# MINIRACER-IMU.net
KiCad netlist of a schematic drawn in Altium Designer
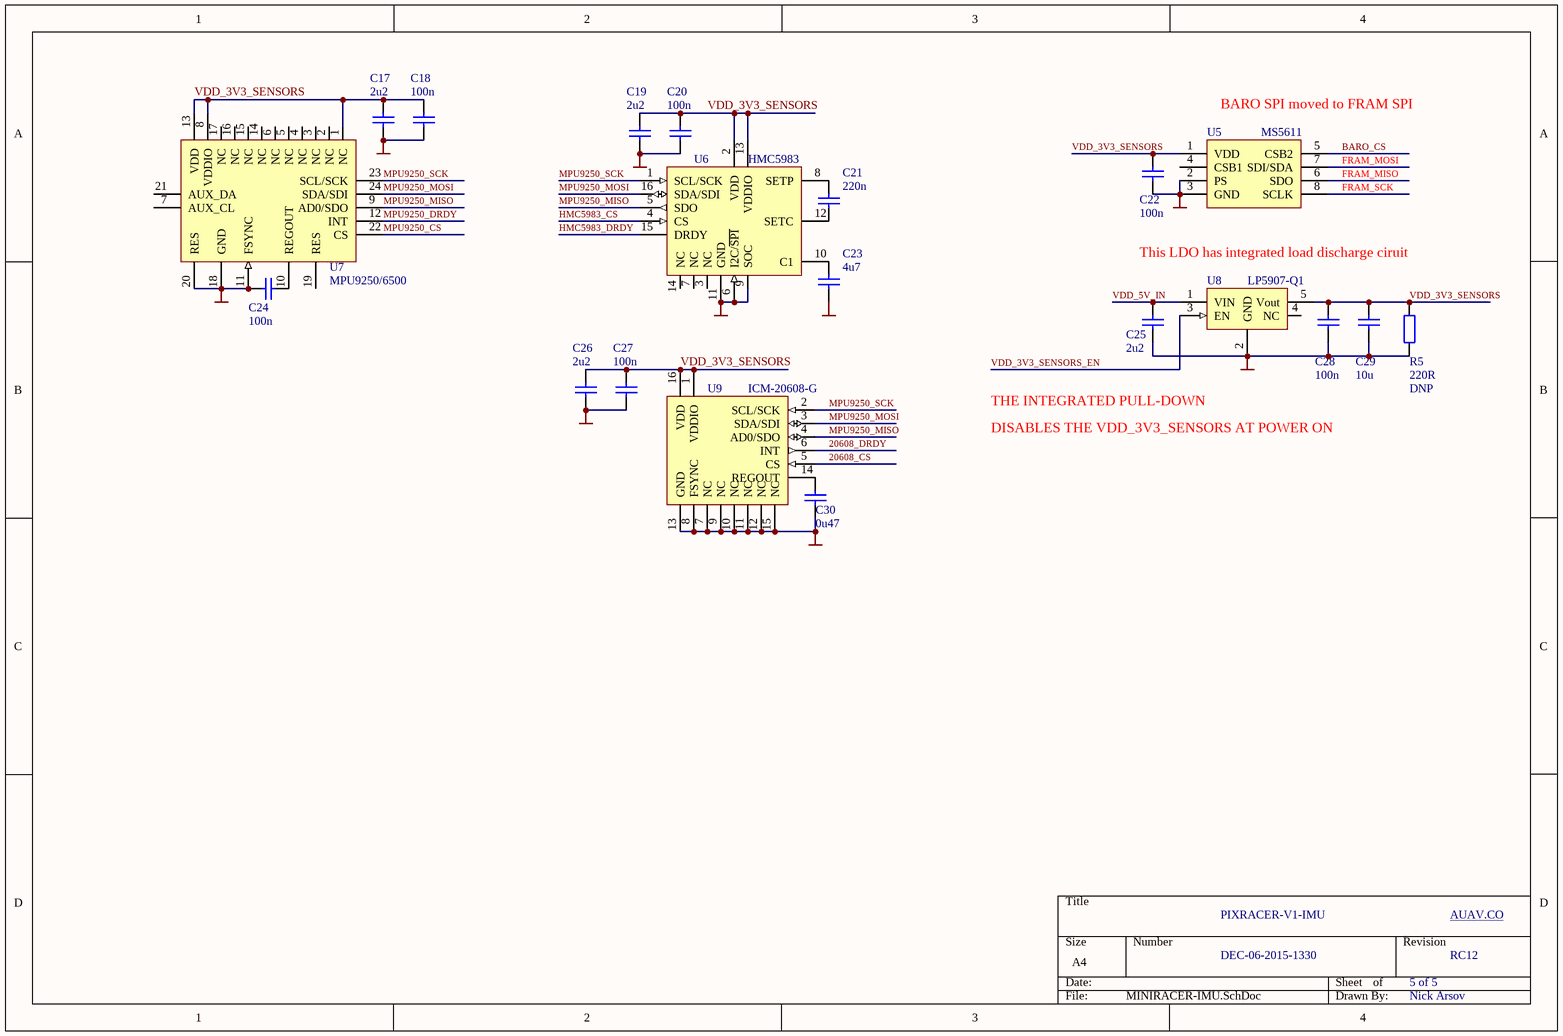
[diagram p0: MINIRACER-IMU.SchDoc]

(export (version "E")
  (design (tool "Eeschema 10.0.6"))
  (components
    (comp (ref "C17")
      (value "2u2")
      (footprint "0402A")
      (description "Capacitor")
      (fields (field (name "PUBLISHER") "Altium Limited"))
      (libsource (lib "Miscellaneous Devices") (part "Cap"))
    )
    (comp (ref "C18")
      (value "100n")
      (footprint "0402A")
      (description "Capacitor")
      (fields (field (name "PUBLISHER") "Altium Limited"))
      (libsource (lib "Miscellaneous Devices") (part "Cap"))
    )
    (comp (ref "C19")
      (value "2u2")
      (footprint "0402A")
      (description "Capacitor")
      (fields (field (name "PUBLISHER") "Altium Limited"))
      (libsource (lib "Miscellaneous Devices") (part "Cap"))
    )
    (comp (ref "C20")
      (value "100n")
      (footprint "0402A")
      (description "Capacitor")
      (fields (field (name "PUBLISHER") "Altium Limited"))
      (libsource (lib "Miscellaneous Devices") (part "Cap"))
    )
    (comp (ref "C21")
      (value "220n")
      (footprint "0402A")
      (description "Capacitor")
      (fields (field (name "PUBLISHER") "Altium Limited"))
      (libsource (lib "Miscellaneous Devices") (part "Cap"))
    )
    (comp (ref "C22")
      (value "100n")
      (footprint "0402A")
      (description "Capacitor")
      (fields (field (name "PUBLISHER") "Altium Limited"))
      (libsource (lib "Miscellaneous Devices") (part "Cap"))
    )
    (comp (ref "C23")
      (value "4u7")
      (footprint "0603A")
      (description "Capacitor")
      (fields (field (name "PUBLISHER") "Altium Limited"))
      (libsource (lib "Miscellaneous Devices") (part "Cap"))
    )
    (comp (ref "C24")
      (value "100n")
      (footprint "0402A")
      (description "Capacitor")
      (fields (field (name "PUBLISHER") "Altium Limited"))
      (libsource (lib "Miscellaneous Devices") (part "Cap"))
    )
    (comp (ref "C25")
      (value "2u2")
      (footprint "0603A")
      (description "Capacitor")
      (fields (field (name "PUBLISHER") "Altium Limited"))
      (libsource (lib "Miscellaneous Devices") (part "Cap"))
    )
    (comp (ref "C26")
      (value "2u2")
      (footprint "0402A")
      (description "Capacitor")
      (fields (field (name "PUBLISHER") "Altium Limited"))
      (libsource (lib "Miscellaneous Devices") (part "Cap"))
    )
    (comp (ref "C27")
      (value "100n")
      (footprint "0402A")
      (description "Capacitor")
      (fields (field (name "PUBLISHER") "Altium Limited"))
      (libsource (lib "Miscellaneous Devices") (part "Cap"))
    )
    (comp (ref "C28")
      (value "100n")
      (footprint "0603A")
      (description "Capacitor")
      (fields (field (name "PUBLISHER") "Altium Limited"))
      (libsource (lib "Miscellaneous Devices") (part "Cap"))
    )
    (comp (ref "C29")
      (value "10u")
      (footprint "0603A")
      (description "Capacitor")
      (fields (field (name "PUBLISHER") "Altium Limited"))
      (libsource (lib "Miscellaneous Devices") (part "Cap"))
    )
    (comp (ref "C30")
      (value "0u47")
      (footprint "0402A")
      (description "Capacitor")
      (fields (field (name "PUBLISHER") "Altium Limited"))
      (libsource (lib "Miscellaneous Devices") (part "Cap"))
    )
    (comp (ref "R5")
      (value "220R")
      (footprint "0402A")
      (description "Resistor")
      (fields (field (name "REM") "DNP") (field (name "PUBLISHER") "Altium Limited"))
      (libsource (lib "Miscellaneous Devices") (part "Res2"))
    )
    (comp (ref "U5")
      (value "MS5611")
      (footprint "MS5611")
      (libsource (lib "My_Altium") (part "MS5611-01BA03"))
    )
    (comp (ref "U6") (value "HMC5983") (footprint "HMC5883L") (libsource (lib "My_Altium") (part "HMC5983")))
    (comp (ref "U7")
      (value "MPU9250/6500")
      (footprint "MPU6500-9250")
      (libsource (lib "My_Altium") (part "MPU6500"))
    )
    (comp (ref "U8")
      (value "LP5907-Q1")
      (footprint "SOT23-5")
      (libsource (lib "My_Altium") (part "LP5907-Q1"))
    )
    (comp (ref "U9")
      (value "ICM-20608-G")
      (footprint "HCLGA-16L")
      (libsource (lib "My_Altium") (part "ICM-20608-G"))
    )
  )
  (nets
    (net (code "1") (name "/20608_CS") (class "Default")
      (node (ref "U9") (pin "5") (pinfunction "CS_5") (pintype "input"))
    )
    (net (code "2") (name "/20608_DRDY") (class "Default")
      (node (ref "U9") (pin "6") (pinfunction "INT_6") (pintype "output"))
    )
    (net (code "3") (name "/BARO_CS") (class "Default")
      (node (ref "U5") (pin "5") (pinfunction "CSB2_5") (pintype "passive"))
    )
    (net (code "4") (name "/FRAM_MISO") (class "Default")
      (node (ref "U5") (pin "6") (pinfunction "SDO_6") (pintype "passive"))
    )
    (net (code "5") (name "/FRAM_MOSI") (class "Default")
      (node (ref "U5") (pin "7") (pinfunction "SDI/SDA_7") (pintype "passive"))
    )
    (net (code "6") (name "/FRAM_SCK") (class "Default")
      (node (ref "U5") (pin "8") (pinfunction "SCLK_8") (pintype "passive"))
    )
    (net (code "7") (name "/HMC5983_CS") (class "Default")
      (node (ref "U6") (pin "4") (pinfunction "CS_4") (pintype "input"))
    )
    (net (code "8") (name "/HMC5983_DRDY") (class "Default")
      (node (ref "U6") (pin "15") (pinfunction "DRDY_15") (pintype "passive"))
    )
    (net (code "9") (name "/MPU9250_CS") (class "Default")
      (node (ref "U7") (pin "22") (pinfunction "CS_22") (pintype "passive"))
    )
    (net (code "10") (name "/MPU9250_DRDY") (class "Default")
      (node (ref "U7") (pin "12") (pinfunction "INT_12") (pintype "passive"))
    )
    (net (code "11") (name "/MPU9250_MISO") (class "Default")
      (node (ref "U6") (pin "5") (pinfunction "SDO_5") (pintype "output"))
      (node (ref "U7") (pin "9") (pinfunction "AD0/SDO_9") (pintype "passive"))
      (node (ref "U9") (pin "4") (pinfunction "AD0/SDO_4") (pintype "bidirectional"))
    )
    (net (code "12") (name "/MPU9250_MOSI") (class "Default")
      (node (ref "U6") (pin "16") (pinfunction "SDA/SDI_16") (pintype "bidirectional"))
      (node (ref "U7") (pin "24") (pinfunction "SDA/SDI_24") (pintype "passive"))
      (node (ref "U9") (pin "3") (pinfunction "SDA/SDI_3") (pintype "bidirectional"))
    )
    (net (code "13") (name "/MPU9250_SCK") (class "Default")
      (node (ref "U6") (pin "1") (pinfunction "SCL/SCK_1") (pintype "input"))
      (node (ref "U7") (pin "23") (pinfunction "SCL/SCK_23") (pintype "passive"))
      (node (ref "U9") (pin "2") (pinfunction "SCL/SCK_2") (pintype "input"))
    )
    (net (code "14") (name "/VDD_3V3_SENSORS") (class "Default")
      (node (ref "C17") (pin "2") (pinfunction "2_2") (pintype "passive"))
      (node (ref "C18") (pin "2") (pinfunction "2_2") (pintype "passive"))
      (node (ref "C19") (pin "2") (pinfunction "2_2") (pintype "passive"))
      (node (ref "C20") (pin "2") (pinfunction "2_2") (pintype "passive"))
      (node (ref "C22") (pin "2") (pinfunction "2_2") (pintype "passive"))
      (node (ref "C26") (pin "2") (pinfunction "2_2") (pintype "passive"))
      (node (ref "C27") (pin "2") (pinfunction "2_2") (pintype "passive"))
      (node (ref "C28") (pin "2") (pinfunction "2_2") (pintype "passive"))
      (node (ref "C29") (pin "2") (pinfunction "2_2") (pintype "passive"))
      (node (ref "R5") (pin "2") (pinfunction "2_2") (pintype "passive"))
      (node (ref "U5") (pin "1") (pinfunction "VDD_1") (pintype "power_in"))
      (node (ref "U6") (pin "13") (pinfunction "VDDIO_13") (pintype "power_in"))
      (node (ref "U6") (pin "2") (pinfunction "VDD_2") (pintype "power_in"))
      (node (ref "U7") (pin "1") (pinfunction "NC_1") (pintype "passive"))
      (node (ref "U7") (pin "13") (pinfunction "VDD_13") (pintype "power_in"))
      (node (ref "U7") (pin "8") (pinfunction "VDDIO_8") (pintype "power_in"))
      (node (ref "U8") (pin "5") (pinfunction "Vout_5") (pintype "power_in"))
      (node (ref "U9") (pin "1") (pinfunction "VDDIO_1") (pintype "power_in"))
      (node (ref "U9") (pin "16") (pinfunction "VDD_16") (pintype "power_in"))
    )
    (net (code "15") (name "/VDD_3V3_SENSORS_EN") (class "Default")
      (node (ref "U8") (pin "3") (pinfunction "EN_3") (pintype "input"))
    )
    (net (code "16") (name "/VDD_5V_IN") (class "Default")
      (node (ref "C25") (pin "2") (pinfunction "2_2") (pintype "passive"))
      (node (ref "U8") (pin "1") (pinfunction "VIN_1") (pintype "power_in"))
    )
    (net (code "17") (name "GND") (class "Default")
      (node (ref "C17") (pin "1") (pinfunction "1_1") (pintype "passive"))
      (node (ref "C18") (pin "1") (pinfunction "1_1") (pintype "passive"))
      (node (ref "C19") (pin "1") (pinfunction "1_1") (pintype "passive"))
      (node (ref "C20") (pin "1") (pinfunction "1_1") (pintype "passive"))
      (node (ref "C22") (pin "1") (pinfunction "1_1") (pintype "passive"))
      (node (ref "C23") (pin "1") (pinfunction "1_1") (pintype "passive"))
      (node (ref "C24") (pin "1") (pinfunction "1_1") (pintype "passive"))
      (node (ref "C25") (pin "1") (pinfunction "1_1") (pintype "passive"))
      (node (ref "C26") (pin "1") (pinfunction "1_1") (pintype "passive"))
      (node (ref "C27") (pin "1") (pinfunction "1_1") (pintype "passive"))
      (node (ref "C28") (pin "1") (pinfunction "1_1") (pintype "passive"))
      (node (ref "C29") (pin "1") (pinfunction "1_1") (pintype "passive"))
      (node (ref "C30") (pin "1") (pinfunction "1_1") (pintype "passive"))
      (node (ref "R5") (pin "1") (pinfunction "1_1") (pintype "passive"))
      (node (ref "U5") (pin "2") (pinfunction "PS_2") (pintype "passive"))
      (node (ref "U5") (pin "3") (pinfunction "GND_3") (pintype "power_in"))
      (node (ref "U6") (pin "11") (pinfunction "GND_11") (pintype "power_in"))
      (node (ref "U6") (pin "6") (pinfunction "I2C/~{SPI}_6") (pintype "input"))
      (node (ref "U6") (pin "9") (pinfunction "SOC_9") (pintype "power_in"))
      (node (ref "U7") (pin "11") (pinfunction "FSYNC_11") (pintype "input"))
      (node (ref "U7") (pin "18") (pinfunction "GND_18") (pintype "power_in"))
      (node (ref "U7") (pin "20") (pinfunction "RES_20") (pintype "passive"))
      (node (ref "U8") (pin "2") (pinfunction "GND_2") (pintype "power_in"))
      (node (ref "U9") (pin "10") (pinfunction "NC_10") (pintype "passive"))
      (node (ref "U9") (pin "11") (pinfunction "NC_11") (pintype "passive"))
      (node (ref "U9") (pin "12") (pinfunction "NC_12") (pintype "passive"))
      (node (ref "U9") (pin "13") (pinfunction "GND_13") (pintype "power_in"))
      (node (ref "U9") (pin "15") (pinfunction "NC_15") (pintype "passive"))
      (node (ref "U9") (pin "7") (pinfunction "NC_7") (pintype "passive"))
      (node (ref "U9") (pin "8") (pinfunction "FSYNC_8") (pintype "passive"))
      (node (ref "U9") (pin "9") (pinfunction "NC_9") (pintype "passive"))
    )
    (net (code "18") (name "Net-(U6-C1)") (class "Default")
      (node (ref "C23") (pin "2") (pinfunction "2_2") (pintype "passive"))
      (node (ref "U6") (pin "10") (pinfunction "C1_10") (pintype "passive"))
    )
    (net (code "19") (name "Net-(U6-SETC)") (class "Default")
      (node (ref "C21") (pin "1") (pinfunction "1_1") (pintype "passive"))
      (node (ref "U6") (pin "12") (pinfunction "SETC_12") (pintype "passive"))
    )
    (net (code "20") (name "Net-(U6-SETP)") (class "Default")
      (node (ref "C21") (pin "2") (pinfunction "2_2") (pintype "passive"))
      (node (ref "U6") (pin "8") (pinfunction "SETP_8") (pintype "passive"))
    )
    (net (code "21") (name "Net-(U7-REGOUT)") (class "Default")
      (node (ref "C24") (pin "2") (pinfunction "2_2") (pintype "passive"))
      (node (ref "U7") (pin "10") (pinfunction "REGOUT_10") (pintype "passive"))
    )
    (net (code "22") (name "Net-(U9-REGOUT)") (class "Default")
      (node (ref "C30") (pin "2") (pinfunction "2_2") (pintype "passive"))
      (node (ref "U9") (pin "14") (pinfunction "REGOUT_14") (pintype "passive"))
    )
    (net (code "23") (name "unconnected-(U5-CSB1-Pad4)") (class "Default")
      (node (ref "U5") (pin "4") (pinfunction "CSB1_4") (pintype "passive"))
    )
    (net (code "24") (name "unconnected-(U6-NC-Pad3)") (class "Default")
      (node (ref "U6") (pin "3") (pinfunction "NC_3") (pintype "passive"))
    )
    (net (code "25") (name "unconnected-(U6-NC-Pad7)") (class "Default")
      (node (ref "U6") (pin "7") (pinfunction "NC_7") (pintype "passive"))
    )
    (net (code "26") (name "unconnected-(U6-NC-Pad14)") (class "Default")
      (node (ref "U6") (pin "14") (pinfunction "NC_14") (pintype "passive"))
    )
    (net (code "27") (name "unconnected-(U7-AUX_CL-Pad7)") (class "Default")
      (node (ref "U7") (pin "7") (pinfunction "AUX_CL_7") (pintype "passive"))
    )
    (net (code "28") (name "unconnected-(U7-AUX_DA-Pad21)") (class "Default")
      (node (ref "U7") (pin "21") (pinfunction "AUX_DA_21") (pintype "passive"))
    )
    (net (code "29") (name "unconnected-(U7-NC-Pad2)") (class "Default")
      (node (ref "U7") (pin "2") (pinfunction "NC_2") (pintype "passive"))
    )
    (net (code "30") (name "unconnected-(U7-NC-Pad3)") (class "Default")
      (node (ref "U7") (pin "3") (pinfunction "NC_3") (pintype "passive"))
    )
    (net (code "31") (name "unconnected-(U7-NC-Pad4)") (class "Default")
      (node (ref "U7") (pin "4") (pinfunction "NC_4") (pintype "passive"))
    )
    (net (code "32") (name "unconnected-(U7-NC-Pad5)") (class "Default")
      (node (ref "U7") (pin "5") (pinfunction "NC_5") (pintype "passive"))
    )
    (net (code "33") (name "unconnected-(U7-NC-Pad6)") (class "Default")
      (node (ref "U7") (pin "6") (pinfunction "NC_6") (pintype "passive"))
    )
    (net (code "34") (name "unconnected-(U7-NC-Pad14)") (class "Default")
      (node (ref "U7") (pin "14") (pinfunction "NC_14") (pintype "passive"))
    )
    (net (code "35") (name "unconnected-(U7-NC-Pad15)") (class "Default")
      (node (ref "U7") (pin "15") (pinfunction "NC_15") (pintype "passive"))
    )
    (net (code "36") (name "unconnected-(U7-NC-Pad16)") (class "Default")
      (node (ref "U7") (pin "16") (pinfunction "NC_16") (pintype "passive"))
    )
    (net (code "37") (name "unconnected-(U7-NC-Pad17)") (class "Default")
      (node (ref "U7") (pin "17") (pinfunction "NC_17") (pintype "passive"))
    )
    (net (code "38") (name "unconnected-(U7-RES-Pad19)") (class "Default")
      (node (ref "U7") (pin "19") (pinfunction "RES_19") (pintype "passive"))
    )
    (net (code "39") (name "unconnected-(U8-NC-Pad4)") (class "Default")
      (node (ref "U8") (pin "4") (pinfunction "NC_4") (pintype "passive"))
    )
  )
)
